# PCB__CSPS__ESP32.net
KiCad netlist of a schematic drawn in Altium Designer
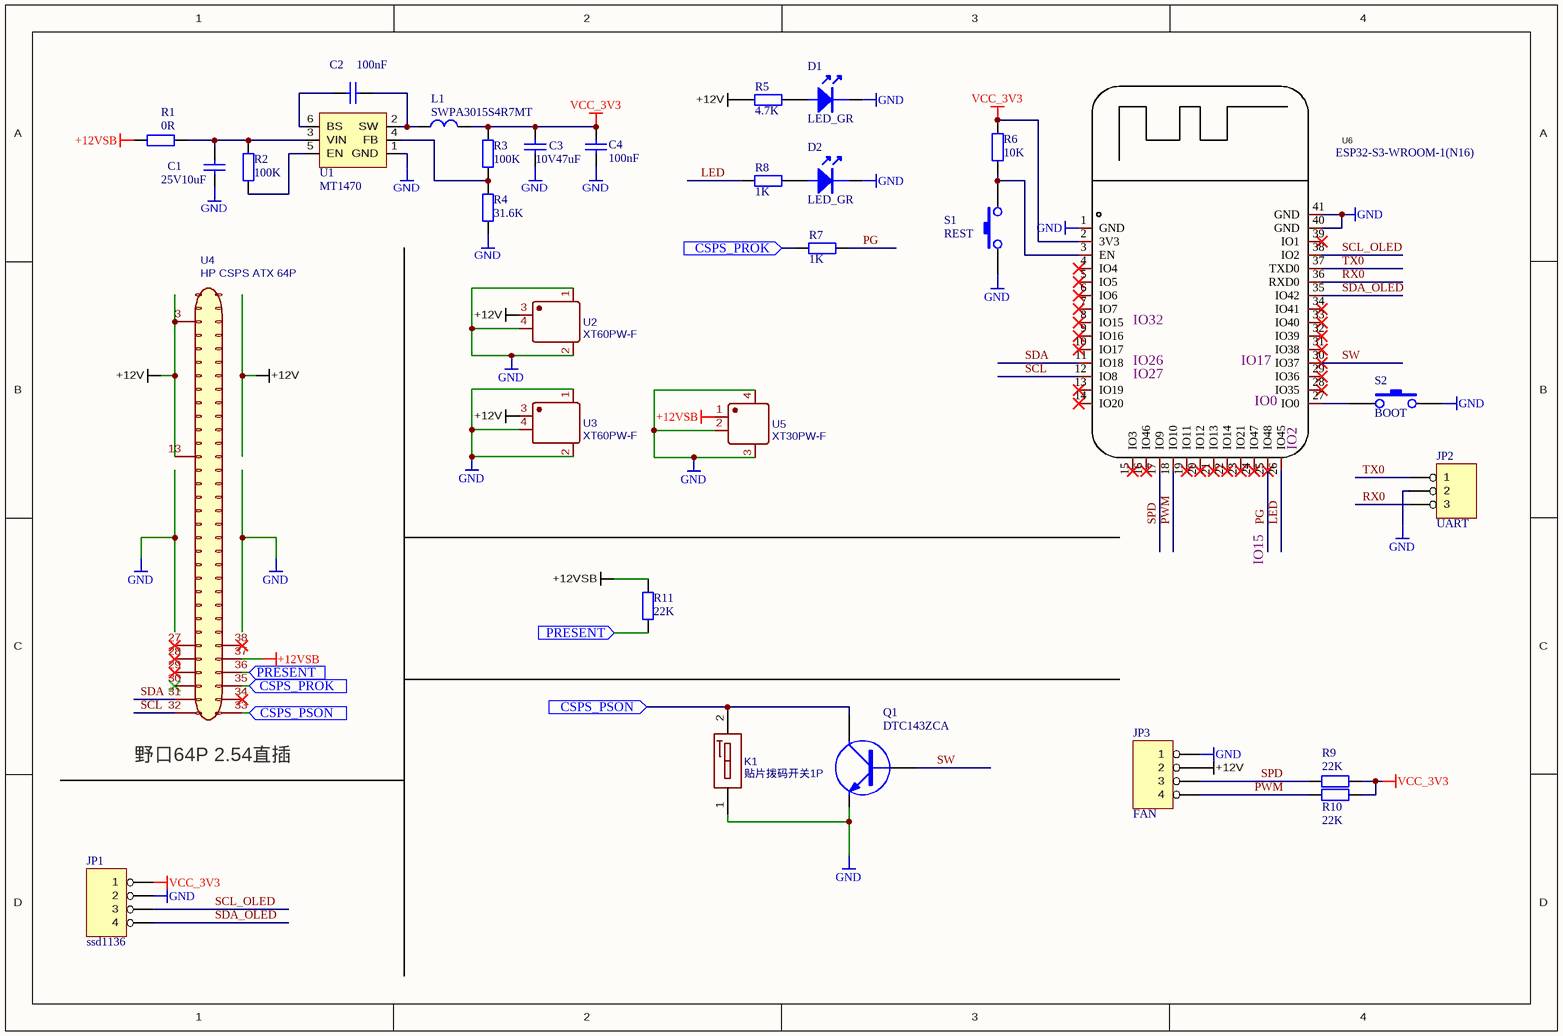
[diagram p0: PCB_热插拔CSPS电源背板_ESP32.schdoc]

(export (version "E")
  (design (tool "Eeschema 10.0.6"))
  (components
    (comp (ref "C1")
      (value "25V10uF")
      (footprint "1206C")
      (description "Capacitor")
      (libsource (lib "Miscellaneous Devices") (part "Cap"))
    )
    (comp (ref "C2")
      (value "100nF")
      (footprint "0603C")
      (description "Capacitor")
      (libsource (lib "Miscellaneous Devices") (part "Cap"))
    )
    (comp (ref "C3")
      (value "10V47uF")
      (footprint "1206C")
      (description "Capacitor")
      (libsource (lib "Miscellaneous Devices") (part "Cap"))
    )
    (comp (ref "C4")
      (value "100nF")
      (footprint "0603C")
      (description "Capacitor")
      (libsource (lib "Miscellaneous Devices") (part "Cap"))
    )
    (comp (ref "D1") (value "LED_GR") (footprint "LED-SMD-0603") (libsource (lib "U_PP SCH") (part "LED")))
    (comp (ref "D2") (value "LED_GR") (footprint "LED-SMD-0603") (libsource (lib "U_PP SCH") (part "LED")))
    (comp (ref "JP1") (value "ssd1136") (footprint "SIP4") (libsource (lib "U_PP SCH") (part "HEADER4")))
    (comp (ref "JP2") (value "UART") (footprint "SIP3") (libsource (lib "U_PP SCH") (part "HEADER 3")))
    (comp (ref "JP3") (value "FAN") (footprint "PH2.0-4AW") (libsource (lib "U_PP SCH") (part "HEADER4")))
    (comp (ref "K1")
      (value "贴片拨码开关1P")
      (footprint "贴片拨码开关1P")
      (fields (field (name "CONTRIBUTOR") "HalfSweet"))
      (libsource (lib "altium-import") (part "root_1_贴片拨码开关1P_"))
    )
    (comp (ref "L1")
      (value "SWPA3015S4R7MT")
      (footprint "COKE_3X3A")
      (libsource (lib "U_PP SCH") (part "INDUCTOR"))
    )
    (comp (ref "Q1")
      (value "DTC143ZCA")
      (footprint "SOT23")
      (description "NPN Transistor")
      (libsource (lib "U_PP SCH") (part "NPN"))
    )
    (comp (ref "R1")
      (value "0R")
      (footprint "0603R")
      (description "Resistor")
      (libsource (lib "Miscellaneous Devices") (part "Res2"))
    )
    (comp (ref "R2")
      (value "100K")
      (footprint "0603R")
      (description "Resistor")
      (libsource (lib "") (part "Res2_1"))
    )
    (comp (ref "R3")
      (value "100K")
      (footprint "0603R")
      (description "Resistor")
      (libsource (lib "") (part "Res2_1"))
    )
    (comp (ref "R4")
      (value "31.6K")
      (footprint "0603R")
      (description "Resistor")
      (libsource (lib "") (part "Res2_1"))
    )
    (comp (ref "R5")
      (value "4.7K")
      (footprint "0603R")
      (description "Resistor")
      (libsource (lib "Miscellaneous Devices") (part "Res2"))
    )
    (comp (ref "R6")
      (value "10K")
      (footprint "0603R")
      (description "Resistor")
      (libsource (lib "") (part "Res2_2"))
    )
    (comp (ref "R7")
      (value "1K")
      (footprint "0603R")
      (description "Resistor")
      (libsource (lib "Miscellaneous Devices") (part "Res2"))
    )
    (comp (ref "R8")
      (value "1K")
      (footprint "0603R")
      (description "Resistor")
      (libsource (lib "Miscellaneous Devices") (part "Res2"))
    )
    (comp (ref "R9")
      (value "22K")
      (footprint "0603R")
      (description "Resistor")
      (libsource (lib "") (part "Res2_3"))
    )
    (comp (ref "R10")
      (value "22K")
      (footprint "0603R")
      (description "Resistor")
      (libsource (lib "") (part "Res2_3"))
    )
    (comp (ref "R11")
      (value "22K")
      (footprint "0603R")
      (description "Resistor")
      (libsource (lib "") (part "Res2_2"))
    )
    (comp (ref "S1") (value "REST") (footprint "KEY-3.6X6") (libsource (lib "U_PP SCH") (part "SW-PB")))
    (comp (ref "S2") (value "BOOT") (footprint "KEY-3.6X6") (libsource (lib "U_PP SCH") (part "SW-PB")))
    (comp (ref "U1") (value "MT1470") (footprint "SOT23-6") (libsource (lib "U_PP SCH") (part "MT1470")))
    (comp (ref "U2")
      (value "XT60PW-F")
      (footprint "TH_2P-XT60PW-F")
      (fields
        (field (name "BOM_SUPPLIER PART") "C9900000737")
        (field (name "BOM_MANUFACTURER PART") "XT60PW-F 母头 板插卧式")
        (field (name "CONTRIBUTOR") "LCSC")
      )
      (libsource (lib "altium-import") (part "root_0_XT60PW-F_"))
    )
    (comp (ref "U3")
      (value "XT60PW-F")
      (footprint "TH_2P-XT60PW-F")
      (fields
        (field (name "BOM_SUPPLIER PART") "C9900000737")
        (field (name "BOM_MANUFACTURER PART") "XT60PW-F 母头 板插卧式")
        (field (name "CONTRIBUTOR") "LCSC")
      )
      (libsource (lib "altium-import") (part "root_0_XT60PW-F_"))
    )
    (comp (ref "U4")
      (value "HP CSPS ATX 64P")
      (footprint "ATX 64P HP 野口64P直插")
      (fields (field (name "CONTRIBUTOR") "chaoser"))
      (libsource (lib "altium-import") (part "root_0_HP CSPS ATX 64P_"))
    )
    (comp (ref "U5")
      (value "XT30PW-F")
      (footprint "CONN-TH_XT30PW-F")
      (fields (field (name "BOM_SUPPLIER PART") "C2913282") (field (name "CONTRIBUTOR") "LCSC"))
      (libsource (lib "altium-import") (part "root_0_XT30PW-F_"))
    )
    (comp (ref "U6")
      (value "ESP32-S3-WROOM-1(N16)")
      (footprint "WIRELM-SMD_ESP32-S3-WROOM-1")
      (fields (field (name "DESIGNER") "U?"))
      (libsource (lib "altium-import") (part "root_0_ESP32-S3-WROOM-1(N16)_"))
    )
  )
  (nets
    (net (code "1") (name "+12V") (class "Default")
      (node (ref "JP3") (pin "2") (pinfunction "2_2") (pintype "passive"))
      (node (ref "R5") (pin "2") (pinfunction "2_2") (pintype "passive"))
      (node (ref "U2") (pin "3") (pinfunction "3_3") (pintype "passive"))
      (node (ref "U3") (pin "3") (pinfunction "3_3") (pintype "passive"))
      (node (ref "U4") (pin "13") (pinfunction "Pin_13_13") (pintype "passive"))
      (node (ref "U4") (pin "3") (pinfunction "Pin_3_3") (pintype "passive"))
    )
    (net (code "2") (name "+12VSB") (class "Default")
      (node (ref "R1") (pin "2") (pinfunction "2_2") (pintype "passive"))
      (node (ref "R11") (pin "1") (pinfunction "1_1") (pintype "passive"))
      (node (ref "U4") (pin "37") (pinfunction "+12VSB_37") (pintype "passive"))
      (node (ref "U5") (pin "1") (pinfunction "1_1") (pintype "passive"))
    )
    (net (code "3") (name "/CSPS_PROK") (class "Default")
      (node (ref "R7") (pin "2") (pinfunction "2_2") (pintype "passive"))
      (node (ref "U4") (pin "35") (pinfunction "I2C-GND_35") (pintype "passive"))
    )
    (net (code "4") (name "/CSPS_PSON") (class "Default")
      (node (ref "K1") (pin "2") (pinfunction "B1_2") (pintype "passive"))
      (node (ref "Q1") (pin "3") (pinfunction "C_3") (pintype "passive"))
      (node (ref "U4") (pin "33") (pinfunction "scl_33") (pintype "passive"))
    )
    (net (code "5") (name "/LED") (class "Default")
      (node (ref "R8") (pin "2") (pinfunction "2_2") (pintype "passive"))
      (node (ref "U6") (pin "26") (pinfunction "IO45_26") (pintype "passive"))
    )
    (net (code "6") (name "/PG") (class "Default")
      (node (ref "R7") (pin "1") (pinfunction "1_1") (pintype "passive"))
      (node (ref "U6") (pin "25") (pinfunction "IO48_25") (pintype "passive"))
    )
    (net (code "7") (name "/PRESENT") (class "Default")
      (node (ref "R11") (pin "2") (pinfunction "2_2") (pintype "passive"))
      (node (ref "U4") (pin "36") (pinfunction "PRESENT_36") (pintype "passive"))
    )
    (net (code "8") (name "/PWM") (class "Default")
      (node (ref "JP3") (pin "4") (pinfunction "4_4") (pintype "passive"))
      (node (ref "R10") (pin "1") (pinfunction "1_1") (pintype "passive"))
      (node (ref "U6") (pin "18") (pinfunction "IO10_18") (pintype "passive"))
    )
    (net (code "9") (name "/RX0") (class "Default")
      (node (ref "JP2") (pin "3") (pinfunction "3_3") (pintype "passive"))
      (node (ref "U6") (pin "36") (pinfunction "RXD0_36") (pintype "passive"))
    )
    (net (code "10") (name "/SCL") (class "Default")
      (node (ref "U4") (pin "32") (pinfunction "CSPS-PSON_32") (pintype "passive"))
      (node (ref "U6") (pin "12") (pinfunction "IO8_12") (pintype "passive"))
    )
    (net (code "11") (name "/SCL_OLED") (class "Default")
      (node (ref "JP1") (pin "3") (pinfunction "3_3") (pintype "passive"))
      (node (ref "U6") (pin "38") (pinfunction "IO2_38") (pintype "passive"))
    )
    (net (code "12") (name "/SDA") (class "Default")
      (node (ref "U4") (pin "31") (pinfunction "Pin_31_31") (pintype "passive"))
      (node (ref "U6") (pin "11") (pinfunction "IO18_11") (pintype "passive"))
    )
    (net (code "13") (name "/SDA_OLED") (class "Default")
      (node (ref "JP1") (pin "4") (pinfunction "4_4") (pintype "passive"))
      (node (ref "U6") (pin "35") (pinfunction "IO42_35") (pintype "passive"))
    )
    (net (code "14") (name "/SPD") (class "Default")
      (node (ref "JP3") (pin "3") (pinfunction "3_3") (pintype "passive"))
      (node (ref "R9") (pin "1") (pinfunction "1_1") (pintype "passive"))
      (node (ref "U6") (pin "17") (pinfunction "IO9_17") (pintype "passive"))
    )
    (net (code "15") (name "/SW") (class "Default")
      (node (ref "Q1") (pin "1") (pinfunction "B_1") (pintype "passive"))
      (node (ref "U6") (pin "30") (pinfunction "IO37_30") (pintype "passive"))
    )
    (net (code "16") (name "/TX0") (class "Default")
      (node (ref "JP2") (pin "1") (pinfunction "1_1") (pintype "passive"))
      (node (ref "U6") (pin "37") (pinfunction "TXD0_37") (pintype "passive"))
    )
    (net (code "17") (name "GND") (class "Default")
      (node (ref "C1") (pin "2") (pinfunction "2_2") (pintype "passive"))
      (node (ref "C3") (pin "2") (pinfunction "2_2") (pintype "passive"))
      (node (ref "C4") (pin "1") (pinfunction "1_1") (pintype "passive"))
      (node (ref "D1") (pin "2") (pinfunction "2_2") (pintype "passive"))
      (node (ref "D2") (pin "2") (pinfunction "2_2") (pintype "passive"))
      (node (ref "JP1") (pin "2") (pinfunction "2_2") (pintype "passive"))
      (node (ref "JP2") (pin "2") (pinfunction "2_2") (pintype "passive"))
      (node (ref "JP3") (pin "1") (pinfunction "1_1") (pintype "passive"))
      (node (ref "K1") (pin "1") (pinfunction "A1_1") (pintype "passive"))
      (node (ref "Q1") (pin "2") (pinfunction "E_2") (pintype "passive"))
      (node (ref "R4") (pin "1") (pinfunction "1_1") (pintype "passive"))
      (node (ref "S1") (pin "1") (pinfunction "1_1") (pintype "passive"))
      (node (ref "S2") (pin "2") (pinfunction "2_2") (pintype "passive"))
      (node (ref "U1") (pin "1") (pinfunction "GND_1") (pintype "passive"))
      (node (ref "U2") (pin "1") (pinfunction "1_1") (pintype "passive"))
      (node (ref "U2") (pin "2") (pinfunction "2_2") (pintype "passive"))
      (node (ref "U2") (pin "4") (pinfunction "4_4") (pintype "passive"))
      (node (ref "U3") (pin "1") (pinfunction "1_1") (pintype "passive"))
      (node (ref "U3") (pin "2") (pinfunction "2_2") (pintype "passive"))
      (node (ref "U3") (pin "4") (pinfunction "4_4") (pintype "passive"))
      (node (ref "U5") (pin "2") (pinfunction "2_2") (pintype "passive"))
      (node (ref "U5") (pin "3") (pinfunction "3_3") (pintype "passive"))
      (node (ref "U5") (pin "4") (pinfunction "4_4") (pintype "passive"))
      (node (ref "U6") (pin "1") (pinfunction "GND_1") (pintype "passive"))
      (node (ref "U6") (pin "40") (pinfunction "GND_40") (pintype "passive"))
      (node (ref "U6") (pin "41") (pinfunction "GND_41") (pintype "passive"))
    )
    (net (code "18") (name "Net-(D1-Pad1)") (class "Default")
      (node (ref "D1") (pin "1") (pinfunction "1_1") (pintype "passive"))
      (node (ref "R5") (pin "1") (pinfunction "1_1") (pintype "passive"))
    )
    (net (code "19") (name "Net-(D2-Pad1)") (class "Default")
      (node (ref "D2") (pin "1") (pinfunction "1_1") (pintype "passive"))
      (node (ref "R8") (pin "1") (pinfunction "1_1") (pintype "passive"))
    )
    (net (code "20") (name "Net-(U1-BS)") (class "Default")
      (node (ref "C2") (pin "1") (pinfunction "1_1") (pintype "passive"))
      (node (ref "U1") (pin "6") (pinfunction "BS_6") (pintype "passive"))
    )
    (net (code "21") (name "Net-(U1-EN)") (class "Default")
      (node (ref "R2") (pin "1") (pinfunction "1_1") (pintype "passive"))
      (node (ref "U1") (pin "5") (pinfunction "EN_5") (pintype "passive"))
    )
    (net (code "22") (name "Net-(U1-FB)") (class "Default")
      (node (ref "R3") (pin "1") (pinfunction "1_1") (pintype "passive"))
      (node (ref "R4") (pin "2") (pinfunction "2_2") (pintype "passive"))
      (node (ref "U1") (pin "4") (pinfunction "FB_4") (pintype "passive"))
    )
    (net (code "23") (name "Net-(U1-SW)") (class "Default")
      (node (ref "C2") (pin "2") (pinfunction "2_2") (pintype "passive"))
      (node (ref "L1") (pin "1") (pinfunction "1_1") (pintype "passive"))
      (node (ref "U1") (pin "2") (pinfunction "SW_2") (pintype "passive"))
    )
    (net (code "24") (name "Net-(U1-VIN)") (class "Default")
      (node (ref "C1") (pin "1") (pinfunction "1_1") (pintype "passive"))
      (node (ref "R1") (pin "1") (pinfunction "1_1") (pintype "passive"))
      (node (ref "R2") (pin "2") (pinfunction "2_2") (pintype "passive"))
      (node (ref "U1") (pin "3") (pinfunction "VIN_3") (pintype "passive"))
    )
    (net (code "25") (name "Net-(U6-EN)") (class "Default")
      (node (ref "R6") (pin "2") (pinfunction "2_2") (pintype "passive"))
      (node (ref "S1") (pin "2") (pinfunction "2_2") (pintype "passive"))
      (node (ref "U6") (pin "3") (pinfunction "EN_3") (pintype "passive"))
    )
    (net (code "26") (name "Net-(U6-IO0)") (class "Default")
      (node (ref "S2") (pin "1") (pinfunction "1_1") (pintype "passive"))
      (node (ref "U6") (pin "27") (pinfunction "IO0_27") (pintype "passive"))
    )
    (net (code "27") (name "VCC_3V3") (class "Default")
      (node (ref "C3") (pin "1") (pinfunction "1_1") (pintype "passive"))
      (node (ref "C4") (pin "2") (pinfunction "2_2") (pintype "passive"))
      (node (ref "JP1") (pin "1") (pinfunction "1_1") (pintype "passive"))
      (node (ref "L1") (pin "2") (pinfunction "2_2") (pintype "passive"))
      (node (ref "R10") (pin "2") (pinfunction "2_2") (pintype "passive"))
      (node (ref "R3") (pin "2") (pinfunction "2_2") (pintype "passive"))
      (node (ref "R6") (pin "1") (pinfunction "1_1") (pintype "passive"))
      (node (ref "R9") (pin "2") (pinfunction "2_2") (pintype "passive"))
      (node (ref "U6") (pin "2") (pinfunction "3V3_2") (pintype "passive"))
    )
    (net (code "28") (name "unconnected-(U4-+12VSB-Pad28)") (class "Default")
      (node (ref "U4") (pin "28") (pinfunction "+12VSB_28") (pintype "passive+no_connect"))
    )
    (net (code "29") (name "unconnected-(U4-CSPS-PSOK-Pad30)") (class "Default")
      (node (ref "U4") (pin "30") (pinfunction "CSPS-PSOK_30") (pintype "passive+no_connect"))
    )
    (net (code "30") (name "unconnected-(U4-PRESENT-Pad29)") (class "Default")
      (node (ref "U4") (pin "29") (pinfunction "PRESENT_29") (pintype "passive+no_connect"))
    )
    (net (code "31") (name "unconnected-(U4-PWOK-Pad27)") (class "Default")
      (node (ref "U4") (pin "27") (pinfunction "PWOK_27") (pintype "passive+no_connect"))
    )
    (net (code "32") (name "unconnected-(U4-pin_38-Pad38)") (class "Default")
      (node (ref "U4") (pin "38") (pinfunction "pin_38_38") (pintype "passive+no_connect"))
    )
    (net (code "33") (name "unconnected-(U4-sda-Pad34)") (class "Default")
      (node (ref "U4") (pin "34") (pinfunction "sda_34") (pintype "passive+no_connect"))
    )
    (net (code "34") (name "unconnected-(U6-IO1-Pad39)") (class "Default")
      (node (ref "U6") (pin "39") (pinfunction "IO1_39") (pintype "passive+no_connect"))
    )
    (net (code "35") (name "unconnected-(U6-IO3-Pad15)") (class "Default")
      (node (ref "U6") (pin "15") (pinfunction "IO3_15") (pintype "passive+no_connect"))
    )
    (net (code "36") (name "unconnected-(U6-IO4-Pad4)") (class "Default")
      (node (ref "U6") (pin "4") (pinfunction "IO4_4") (pintype "passive+no_connect"))
    )
    (net (code "37") (name "unconnected-(U6-IO5-Pad5)") (class "Default")
      (node (ref "U6") (pin "5") (pinfunction "IO5_5") (pintype "passive+no_connect"))
    )
    (net (code "38") (name "unconnected-(U6-IO6-Pad6)") (class "Default")
      (node (ref "U6") (pin "6") (pinfunction "IO6_6") (pintype "passive+no_connect"))
    )
    (net (code "39") (name "unconnected-(U6-IO7-Pad7)") (class "Default")
      (node (ref "U6") (pin "7") (pinfunction "IO7_7") (pintype "passive+no_connect"))
    )
    (net (code "40") (name "unconnected-(U6-IO11-Pad19)") (class "Default")
      (node (ref "U6") (pin "19") (pinfunction "IO11_19") (pintype "passive+no_connect"))
    )
    (net (code "41") (name "unconnected-(U6-IO12-Pad20)") (class "Default")
      (node (ref "U6") (pin "20") (pinfunction "IO12_20") (pintype "passive+no_connect"))
    )
    (net (code "42") (name "unconnected-(U6-IO13-Pad21)") (class "Default")
      (node (ref "U6") (pin "21") (pinfunction "IO13_21") (pintype "passive+no_connect"))
    )
    (net (code "43") (name "unconnected-(U6-IO14-Pad22)") (class "Default")
      (node (ref "U6") (pin "22") (pinfunction "IO14_22") (pintype "passive+no_connect"))
    )
    (net (code "44") (name "unconnected-(U6-IO15-Pad8)") (class "Default")
      (node (ref "U6") (pin "8") (pinfunction "IO15_8") (pintype "passive+no_connect"))
    )
    (net (code "45") (name "unconnected-(U6-IO16-Pad9)") (class "Default")
      (node (ref "U6") (pin "9") (pinfunction "IO16_9") (pintype "passive+no_connect"))
    )
    (net (code "46") (name "unconnected-(U6-IO17-Pad10)") (class "Default")
      (node (ref "U6") (pin "10") (pinfunction "IO17_10") (pintype "passive+no_connect"))
    )
    (net (code "47") (name "unconnected-(U6-IO19-Pad13)") (class "Default")
      (node (ref "U6") (pin "13") (pinfunction "IO19_13") (pintype "passive+no_connect"))
    )
    (net (code "48") (name "unconnected-(U6-IO20-Pad14)") (class "Default")
      (node (ref "U6") (pin "14") (pinfunction "IO20_14") (pintype "passive+no_connect"))
    )
    (net (code "49") (name "unconnected-(U6-IO21-Pad23)") (class "Default")
      (node (ref "U6") (pin "23") (pinfunction "IO21_23") (pintype "passive+no_connect"))
    )
    (net (code "50") (name "unconnected-(U6-IO35-Pad28)") (class "Default")
      (node (ref "U6") (pin "28") (pinfunction "IO35_28") (pintype "passive+no_connect"))
    )
    (net (code "51") (name "unconnected-(U6-IO36-Pad29)") (class "Default")
      (node (ref "U6") (pin "29") (pinfunction "IO36_29") (pintype "passive+no_connect"))
    )
    (net (code "52") (name "unconnected-(U6-IO38-Pad31)") (class "Default")
      (node (ref "U6") (pin "31") (pinfunction "IO38_31") (pintype "passive+no_connect"))
    )
    (net (code "53") (name "unconnected-(U6-IO39-Pad32)") (class "Default")
      (node (ref "U6") (pin "32") (pinfunction "IO39_32") (pintype "passive+no_connect"))
    )
    (net (code "54") (name "unconnected-(U6-IO40-Pad33)") (class "Default")
      (node (ref "U6") (pin "33") (pinfunction "IO40_33") (pintype "passive+no_connect"))
    )
    (net (code "55") (name "unconnected-(U6-IO41-Pad34)") (class "Default")
      (node (ref "U6") (pin "34") (pinfunction "IO41_34") (pintype "passive+no_connect"))
    )
    (net (code "56") (name "unconnected-(U6-IO46-Pad16)") (class "Default")
      (node (ref "U6") (pin "16") (pinfunction "IO46_16") (pintype "passive+no_connect"))
    )
    (net (code "57") (name "unconnected-(U6-IO47-Pad24)") (class "Default")
      (node (ref "U6") (pin "24") (pinfunction "IO47_24") (pintype "passive+no_connect"))
    )
  )
)
